# Lights.net
KiCad netlist of a schematic drawn in Altium Designer
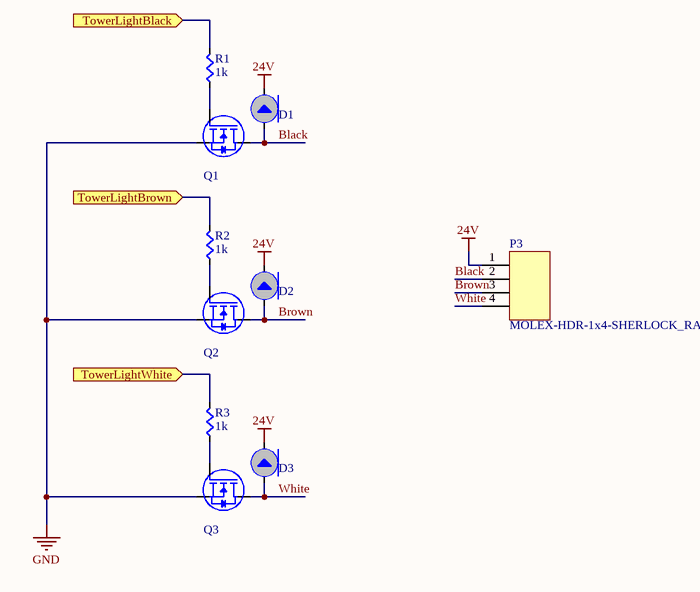
[diagram p0: Lights.SchDoc]

(export (version "E")
  (design (tool "Eeschema 10.0.6"))
  (components
    (comp (ref "D1")
      (value "S1B-13-F")
      (footprint "Semiconductors:SMASeries")
      (description "Standard Diode Template")
      (libsource (lib "Semiconductors") (part "Diode"))
    )
    (comp (ref "D2")
      (value "S1B-13-F")
      (footprint "Semiconductors:SMASeries")
      (description "Standard Diode Template")
      (libsource (lib "Semiconductors") (part "Diode"))
    )
    (comp (ref "D3")
      (value "S1B-13-F")
      (footprint "Semiconductors:SMASeries")
      (description "Standard Diode Template")
      (libsource (lib "Semiconductors") (part "Diode"))
    )
    (comp (ref "P3")
      (value "MOLEX-HDR-1x4-SHERLOCK_RA")
      (footprint "MOLEX-HDR-1X4-SHERLOCK-RA")
      (description "Header, Molex, 2mm Pitch Sherlock Header, Single Row, Horizontal, 4 Circuits, Length 3.3mm")
      (fields (field (name "MANUFACTURER PART NUMBER") "0353630460") (field (name "MANUFACTURER") "Molex"))
      (libsource (lib "Connectors") (part "MOLEX-HDR-1x4-SHERLOCK_RA"))
    )
    (comp (ref "Q1")
      (value "BSN20-7")
      (footprint "Semiconductors:SOT-323")
      (description "NMOSFET Template")
      (libsource (lib "Semiconductors") (part "NMOSFET"))
    )
    (comp (ref "Q2")
      (value "BSN20-7")
      (footprint "Semiconductors:SOT-323")
      (description "NMOSFET Template")
      (libsource (lib "Semiconductors") (part "NMOSFET"))
    )
    (comp (ref "Q3")
      (value "BSN20-7")
      (footprint "Semiconductors:SOT-323")
      (description "NMOSFET Template")
      (libsource (lib "Semiconductors") (part "NMOSFET"))
    )
    (comp (ref "R1")
      (value "1k")
      (footprint "RES0603")
      (fields (field (name "Comment") "Res"))
      (libsource (lib "SubjuGator8") (part "Res"))
    )
    (comp (ref "R2")
      (value "1k")
      (footprint "RES0603")
      (fields (field (name "Comment") "Res"))
      (libsource (lib "SubjuGator8") (part "Res"))
    )
    (comp (ref "R3")
      (value "1k")
      (footprint "RES0603")
      (fields (field (name "Comment") "Res"))
      (libsource (lib "SubjuGator8") (part "Res"))
    )
  )
  (nets
    (net (code "1") (name "/Black") (class "Default")
      (node (ref "D1") (pin "A") (pinfunction "A_A") (pintype "passive"))
      (node (ref "P3") (pin "2") (pinfunction "2_2") (pintype "passive"))
      (node (ref "Q1") (pin "3") (pinfunction "D_3") (pintype "passive"))
    )
    (net (code "2") (name "/Brown") (class "Default")
      (node (ref "D2") (pin "A") (pinfunction "A_A") (pintype "passive"))
      (node (ref "P3") (pin "3") (pinfunction "3_3") (pintype "passive"))
      (node (ref "Q2") (pin "3") (pinfunction "D_3") (pintype "passive"))
    )
    (net (code "3") (name "/TowerLightBlack") (class "Default")
      (node (ref "R1") (pin "1") (pinfunction "A_1") (pintype "passive"))
    )
    (net (code "4") (name "/TowerLightBrown") (class "Default")
      (node (ref "R2") (pin "1") (pinfunction "A_1") (pintype "passive"))
    )
    (net (code "5") (name "/TowerLightWhite") (class "Default")
      (node (ref "R3") (pin "1") (pinfunction "A_1") (pintype "passive"))
    )
    (net (code "6") (name "/White") (class "Default")
      (node (ref "D3") (pin "A") (pinfunction "A_A") (pintype "passive"))
      (node (ref "P3") (pin "4") (pinfunction "4_4") (pintype "passive"))
      (node (ref "Q3") (pin "3") (pinfunction "D_3") (pintype "passive"))
    )
    (net (code "7") (name "24V") (class "Default")
      (node (ref "D1") (pin "C") (pinfunction "C_C") (pintype "passive"))
      (node (ref "D2") (pin "C") (pinfunction "C_C") (pintype "passive"))
      (node (ref "D3") (pin "C") (pinfunction "C_C") (pintype "passive"))
      (node (ref "P3") (pin "1") (pinfunction "1_1") (pintype "passive"))
    )
    (net (code "8") (name "GND") (class "Default")
      (node (ref "Q1") (pin "2") (pinfunction "S_2") (pintype "passive"))
      (node (ref "Q2") (pin "2") (pinfunction "S_2") (pintype "passive"))
      (node (ref "Q3") (pin "2") (pinfunction "S_2") (pintype "passive"))
    )
    (net (code "9") (name "Net-(Q1-G)") (class "Default")
      (node (ref "Q1") (pin "1") (pinfunction "G_1") (pintype "passive"))
      (node (ref "R1") (pin "2") (pinfunction "B_2") (pintype "passive"))
    )
    (net (code "10") (name "Net-(Q2-G)") (class "Default")
      (node (ref "Q2") (pin "1") (pinfunction "G_1") (pintype "passive"))
      (node (ref "R2") (pin "2") (pinfunction "B_2") (pintype "passive"))
    )
    (net (code "11") (name "Net-(Q3-G)") (class "Default")
      (node (ref "Q3") (pin "1") (pinfunction "G_1") (pintype "passive"))
      (node (ref "R3") (pin "2") (pinfunction "B_2") (pintype "passive"))
    )
  )
)
